# Control.net
KiCad netlist of a schematic drawn in Altium Designer
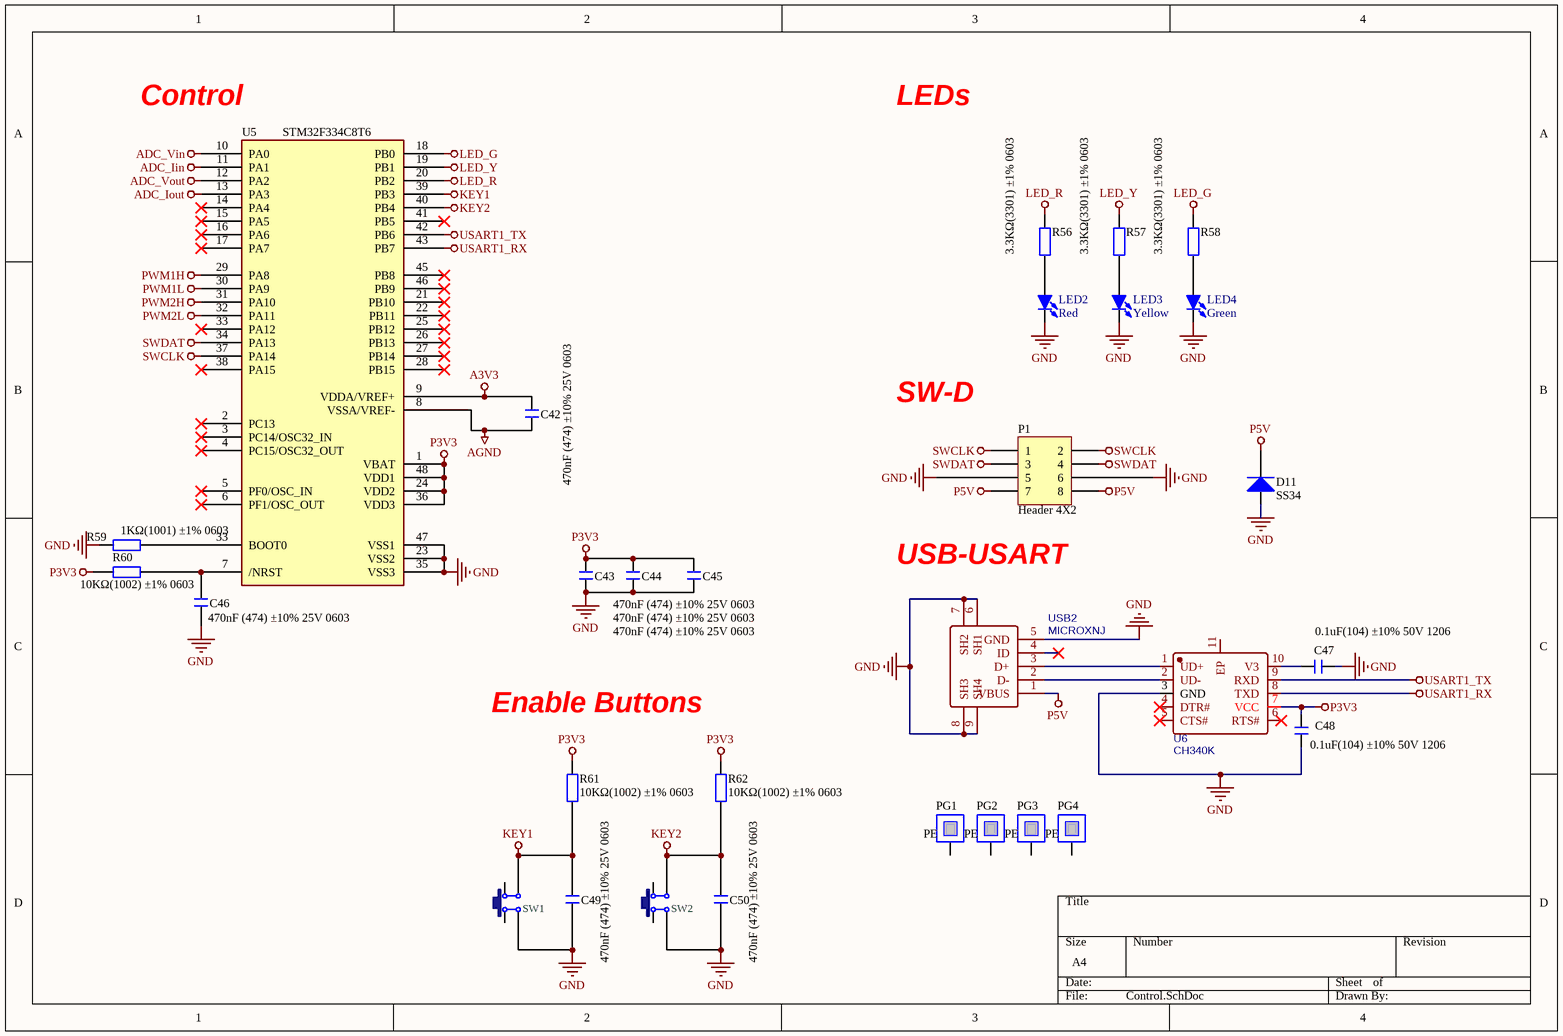
[diagram p0: Control.SchDoc]

(export (version "E")
  (design (tool "Eeschema 10.0.6"))
  (components
    (comp (ref "C42")
      (value "470nF (474) ±10% 25V 0603")
      (footprint "C 0603_L")
      (description "贴片电容")
      (libsource (lib "0.1 - 电阻-电容-电感") (part "C"))
    )
    (comp (ref "C43")
      (value "470nF (474) ±10% 25V 0603")
      (footprint "C 0603_L")
      (description "贴片电容")
      (libsource (lib "0.1 - 电阻-电容-电感") (part "C"))
    )
    (comp (ref "C44")
      (value "470nF (474) ±10% 25V 0603")
      (footprint "C 0603_L")
      (description "贴片电容")
      (libsource (lib "0.1 - 电阻-电容-电感") (part "C"))
    )
    (comp (ref "C45")
      (value "470nF (474) ±10% 25V 0603")
      (footprint "C 0603_L")
      (description "贴片电容")
      (libsource (lib "0.1 - 电阻-电容-电感") (part "C"))
    )
    (comp (ref "C46")
      (value "470nF (474) ±10% 25V 0603")
      (footprint "C 0603_L")
      (description "贴片电容")
      (libsource (lib "0.1 - 电阻-电容-电感") (part "C"))
    )
    (comp (ref "C47")
      (value "0.1uF(104) ±10% 50V 1206")
      (footprint "C 1206_M")
      (description "贴片电容")
      (libsource (lib "0.1 - 电阻-电容-电感") (part "C"))
    )
    (comp (ref "C48")
      (value "0.1uF(104) ±10% 50V 1206")
      (footprint "C 1206_M")
      (description "贴片电容")
      (libsource (lib "0.1 - 电阻-电容-电感") (part "C"))
    )
    (comp (ref "C49")
      (value "470nF (474) ±10% 25V 0603")
      (footprint "C 0603_L")
      (description "贴片电容")
      (libsource (lib "0.1 - 电阻-电容-电感") (part "C"))
    )
    (comp (ref "C50")
      (value "470nF (474) ±10% 25V 0603")
      (footprint "C 0603_L")
      (description "贴片电容")
      (libsource (lib "0.1 - 电阻-电容-电感") (part "C"))
    )
    (comp (ref "D11")
      (value "SS34")
      (footprint "SMA")
      (description "Default Diode")
      (libsource (lib "Miscellaneous Devices") (part "Diode"))
    )
    (comp (ref "LED2")
      (value "Red")
      (footprint "LED 0603R")
      (description "贴片LED")
      (fields (field (name "版权归属") "封装库来自淘宝 ID：黄晶宝石"))
      (libsource (lib "0.3 - LED发光二极管") (part "LED-SMD"))
    )
    (comp (ref "LED3")
      (value "Yellow")
      (footprint "LED 0603R")
      (description "贴片LED")
      (fields (field (name "版权归属") "封装库来自淘宝 ID：黄晶宝石"))
      (libsource (lib "0.3 - LED发光二极管") (part "LED-SMD"))
    )
    (comp (ref "LED4")
      (value "Green")
      (footprint "LED 0603R")
      (description "贴片LED")
      (fields (field (name "版权归属") "封装库来自淘宝 ID：黄晶宝石"))
      (libsource (lib "0.3 - LED发光二极管") (part "LED-SMD"))
    )
    (comp (ref "P1")
      (value "Header 4X2")
      (footprint "HDR2.54-LI-2x4P")
      (description "Header, 4-Pin, Dual row")
      (fields (field (name "PUBLISHER") "Altium Limited"))
      (libsource (lib "Miscellaneous Connectors") (part "Header 4X2"))
    )
    (comp (ref "PG1") (value "PE") (footprint "FG-M3") (libsource (lib "SYMBOL") (part "H-SINK")))
    (comp (ref "PG2") (value "PE") (footprint "FG-M3") (libsource (lib "SYMBOL") (part "H-SINK")))
    (comp (ref "PG3") (value "PE") (footprint "FG-M3") (libsource (lib "SYMBOL") (part "H-SINK")))
    (comp (ref "PG4") (value "PE") (footprint "FG-M3") (libsource (lib "SYMBOL") (part "H-SINK")))
    (comp (ref "R56")
      (value "3.3KΩ(3301) ±1% 0603")
      (footprint "R 0603_L")
      (description "贴片电阻")
      (fields (field (name "版权归属") "来自淘宝 ID：黄晶宝石"))
      (libsource (lib "0.1 - 电阻-电容-电感") (part "R"))
    )
    (comp (ref "R57")
      (value "3.3KΩ(3301) ±1% 0603")
      (footprint "R 0603_L")
      (description "贴片电阻")
      (fields (field (name "版权归属") "来自淘宝 ID：黄晶宝石"))
      (libsource (lib "0.1 - 电阻-电容-电感") (part "R"))
    )
    (comp (ref "R58")
      (value "3.3KΩ(3301) ±1% 0603")
      (footprint "R 0603_L")
      (description "贴片电阻")
      (fields (field (name "版权归属") "来自淘宝 ID：黄晶宝石"))
      (libsource (lib "0.1 - 电阻-电容-电感") (part "R"))
    )
    (comp (ref "R59")
      (value "1KΩ(1001) ±1% 0603")
      (footprint "R 0603_L")
      (description "贴片电阻")
      (fields (field (name "版权归属") "来自淘宝 ID：黄晶宝石"))
      (libsource (lib "0.1 - 电阻-电容-电感") (part "R"))
    )
    (comp (ref "R60")
      (value "10KΩ(1002) ±1% 0603")
      (footprint "R 0603_L")
      (description "贴片电阻")
      (fields (field (name "版权归属") "来自淘宝 ID：黄晶宝石"))
      (libsource (lib "0.1 - 电阻-电容-电感") (part "R"))
    )
    (comp (ref "R61")
      (value "10KΩ(1002) ±1% 0603")
      (footprint "R 0603_L")
      (description "贴片电阻")
      (fields (field (name "版权归属") "来自淘宝 ID：黄晶宝石"))
      (libsource (lib "0.1 - 电阻-电容-电感") (part "R"))
    )
    (comp (ref "R62")
      (value "10KΩ(1002) ±1% 0603")
      (footprint "R 0603_L")
      (description "贴片电阻")
      (fields (field (name "版权归属") "来自淘宝 ID：黄晶宝石"))
      (libsource (lib "0.1 - 电阻-电容-电感") (part "R"))
    )
    (comp (ref "SW1")
      (value "6x6x5")
      (footprint "TSW SMD-6*6*7")
      (description "直插6x6轻触开关")
      (fields (field (name "版权归属") "封装库来自淘宝 ID：黄晶宝石"))
      (libsource (lib "0.7 - 常用按键-开关") (part "TSW DIP-6x6"))
    )
    (comp (ref "SW2")
      (value "6x6x5")
      (footprint "TSW SMD-6*6*7")
      (description "直插6x6轻触开关")
      (fields (field (name "版权归属") "封装库来自淘宝 ID：黄晶宝石"))
      (libsource (lib "0.7 - 常用按键-开关") (part "TSW DIP-6x6"))
    )
    (comp (ref "U5")
      (value "STM32F334C8T6")
      (footprint "LQFP48-7*7")
      (libsource (lib "CBB012DV-V1.0") (part "STM32F334C8T6"))
    )
    (comp (ref "U6")
      (value "CH340K")
      (footprint "ESOP-10_L4.9-W3.9-P1.00-LS6.2-BL-EP")
      (fields (field (name "BOM_SUPPLIER PART") "C968586") (field (name "CONTRIBUTOR") "LCSC"))
      (libsource (lib "Portable power supply") (part "CH340K"))
    )
    (comp (ref "USB2")
      (value "MICROXNJ")
      (footprint "MICRO-USB-SMD_MICROXNJ")
      (fields
        (field (name "BOM_SUPPLIER PART") "C404969")
        (field (name "BOM_MANUFACTURER PART") "MicroXNJ")
        (field (name "CONTRIBUTOR") "LCSC")
      )
      (libsource (lib "Portable power supply") (part "MICROXNJ"))
    )
  )
  (nets
    (net (code "1") (name "A3V3") (class "Default")
      (node (ref "C42") (pin "2") (pinfunction "2_2") (pintype "passive"))
      (node (ref "U5") (pin "9") (pinfunction "VDDA/VREF+_9") (pintype "passive"))
    )
    (net (code "2") (name "ADC_Iin") (class "Default")
      (node (ref "U5") (pin "11") (pinfunction "PA1_11") (pintype "passive"))
    )
    (net (code "3") (name "ADC_Iout") (class "Default")
      (node (ref "U5") (pin "13") (pinfunction "PA3_13") (pintype "passive"))
    )
    (net (code "4") (name "ADC_Vin") (class "Default")
      (node (ref "U5") (pin "10") (pinfunction "PA0_10") (pintype "passive"))
    )
    (net (code "5") (name "ADC_Vout") (class "Default")
      (node (ref "U5") (pin "12") (pinfunction "PA2_12") (pintype "passive"))
    )
    (net (code "6") (name "AGND") (class "Default")
      (node (ref "C42") (pin "1") (pinfunction "1_1") (pintype "passive"))
      (node (ref "U5") (pin "8") (pinfunction "VSSA/VREF-_8") (pintype "passive"))
    )
    (net (code "7") (name "GND") (class "Default")
      (node (ref "C43") (pin "1") (pinfunction "1_1") (pintype "passive"))
      (node (ref "C44") (pin "1") (pinfunction "1_1") (pintype "passive"))
      (node (ref "C45") (pin "1") (pinfunction "1_1") (pintype "passive"))
      (node (ref "C46") (pin "1") (pinfunction "1_1") (pintype "passive"))
      (node (ref "C47") (pin "1") (pinfunction "1_1") (pintype "passive"))
      (node (ref "C48") (pin "2") (pinfunction "2_2") (pintype "passive"))
      (node (ref "C49") (pin "1") (pinfunction "1_1") (pintype "passive"))
      (node (ref "C50") (pin "1") (pinfunction "1_1") (pintype "passive"))
      (node (ref "D11") (pin "1") (pinfunction "A_1") (pintype "passive"))
      (node (ref "LED2") (pin "2") (pinfunction "K_2") (pintype "passive"))
      (node (ref "LED3") (pin "2") (pinfunction "K_2") (pintype "passive"))
      (node (ref "LED4") (pin "2") (pinfunction "K_2") (pintype "passive"))
      (node (ref "P1") (pin "5") (pinfunction "5_5") (pintype "passive"))
      (node (ref "P1") (pin "6") (pinfunction "6_6") (pintype "passive"))
      (node (ref "R59") (pin "1") (pinfunction "1_1") (pintype "passive"))
      (node (ref "SW1") (pin "4") (pinfunction "4_4") (pintype "passive"))
      (node (ref "SW2") (pin "4") (pinfunction "4_4") (pintype "passive"))
      (node (ref "U5") (pin "23") (pinfunction "VSS2_23") (pintype "passive"))
      (node (ref "U5") (pin "35") (pinfunction "VSS3_35") (pintype "passive"))
      (node (ref "U5") (pin "47") (pinfunction "VSS1_47") (pintype "passive"))
      (node (ref "U6") (pin "3") (pinfunction "GND_3") (pintype "passive"))
      (node (ref "USB2") (pin "5") (pinfunction "GND_5") (pintype "passive"))
      (node (ref "USB2") (pin "6") (pinfunction "SH1_6") (pintype "passive"))
      (node (ref "USB2") (pin "7") (pinfunction "SH2_7") (pintype "passive"))
      (node (ref "USB2") (pin "8") (pinfunction "SH3_8") (pintype "passive"))
      (node (ref "USB2") (pin "9") (pinfunction "SH4_9") (pintype "passive"))
    )
    (net (code "8") (name "KEY1") (class "Default")
      (node (ref "C49") (pin "2") (pinfunction "2_2") (pintype "passive"))
      (node (ref "R61") (pin "1") (pinfunction "1_1") (pintype "passive"))
      (node (ref "SW1") (pin "3") (pinfunction "3_3") (pintype "passive"))
      (node (ref "U5") (pin "39") (pinfunction "PB3_39") (pintype "passive"))
    )
    (net (code "9") (name "KEY2") (class "Default")
      (node (ref "C50") (pin "2") (pinfunction "2_2") (pintype "passive"))
      (node (ref "R62") (pin "1") (pinfunction "1_1") (pintype "passive"))
      (node (ref "SW2") (pin "3") (pinfunction "3_3") (pintype "passive"))
      (node (ref "U5") (pin "40") (pinfunction "PB4_40") (pintype "passive"))
    )
    (net (code "10") (name "LED_G") (class "Default")
      (node (ref "R58") (pin "2") (pinfunction "2_2") (pintype "passive"))
      (node (ref "U5") (pin "18") (pinfunction "PB0_18") (pintype "passive"))
    )
    (net (code "11") (name "LED_R") (class "Default")
      (node (ref "R56") (pin "2") (pinfunction "2_2") (pintype "passive"))
      (node (ref "U5") (pin "20") (pinfunction "PB2_20") (pintype "passive"))
    )
    (net (code "12") (name "LED_Y") (class "Default")
      (node (ref "R57") (pin "2") (pinfunction "2_2") (pintype "passive"))
      (node (ref "U5") (pin "19") (pinfunction "PB1_19") (pintype "passive"))
    )
    (net (code "13") (name "Net-(LED2-A)") (class "Default")
      (node (ref "LED2") (pin "1") (pinfunction "A_1") (pintype "passive"))
      (node (ref "R56") (pin "1") (pinfunction "1_1") (pintype "passive"))
    )
    (net (code "14") (name "Net-(LED3-A)") (class "Default")
      (node (ref "LED3") (pin "1") (pinfunction "A_1") (pintype "passive"))
      (node (ref "R57") (pin "1") (pinfunction "1_1") (pintype "passive"))
    )
    (net (code "15") (name "Net-(LED4-A)") (class "Default")
      (node (ref "LED4") (pin "1") (pinfunction "A_1") (pintype "passive"))
      (node (ref "R58") (pin "1") (pinfunction "1_1") (pintype "passive"))
    )
    (net (code "16") (name "Net-(U5-BOOT0)") (class "Default")
      (node (ref "R59") (pin "2") (pinfunction "2_2") (pintype "passive"))
      (node (ref "U5") (pin "33") (pinfunction "BOOT0_33") (pintype "passive"))
    )
    (net (code "17") (name "Net-(U5-{slash}NRST)") (class "Default")
      (node (ref "C46") (pin "2") (pinfunction "2_2") (pintype "passive"))
      (node (ref "R60") (pin "2") (pinfunction "2_2") (pintype "passive"))
      (node (ref "U5") (pin "7") (pinfunction "/NRST_7") (pintype "passive"))
    )
    (net (code "18") (name "Net-(U6-UD+)") (class "Default")
      (node (ref "U6") (pin "1") (pinfunction "UD+_1") (pintype "passive"))
      (node (ref "USB2") (pin "3") (pinfunction "D+_3") (pintype "passive"))
    )
    (net (code "19") (name "Net-(U6-UD-)") (class "Default")
      (node (ref "U6") (pin "2") (pinfunction "UD-_2") (pintype "passive"))
      (node (ref "USB2") (pin "2") (pinfunction "D-_2") (pintype "passive"))
    )
    (net (code "20") (name "Net-(U6-V3)") (class "Default")
      (node (ref "C47") (pin "2") (pinfunction "2_2") (pintype "passive"))
      (node (ref "U6") (pin "10") (pinfunction "V3_10") (pintype "passive"))
    )
    (net (code "21") (name "P3V3") (class "Default")
      (node (ref "C43") (pin "2") (pinfunction "2_2") (pintype "passive"))
      (node (ref "C44") (pin "2") (pinfunction "2_2") (pintype "passive"))
      (node (ref "C45") (pin "2") (pinfunction "2_2") (pintype "passive"))
      (node (ref "C48") (pin "1") (pinfunction "1_1") (pintype "passive"))
      (node (ref "R60") (pin "1") (pinfunction "1_1") (pintype "passive"))
      (node (ref "R61") (pin "2") (pinfunction "2_2") (pintype "passive"))
      (node (ref "R62") (pin "2") (pinfunction "2_2") (pintype "passive"))
      (node (ref "U5") (pin "1") (pinfunction "VBAT_1") (pintype "passive"))
      (node (ref "U5") (pin "24") (pinfunction "VDD2_24") (pintype "passive"))
      (node (ref "U5") (pin "36") (pinfunction "VDD3_36") (pintype "passive"))
      (node (ref "U5") (pin "48") (pinfunction "VDD1_48") (pintype "passive"))
      (node (ref "U6") (pin "7") (pinfunction "VCC_7") (pintype "passive"))
    )
    (net (code "22") (name "P5V") (class "Default")
      (node (ref "D11") (pin "2") (pinfunction "K_2") (pintype "passive"))
      (node (ref "P1") (pin "7") (pinfunction "7_7") (pintype "passive"))
      (node (ref "P1") (pin "8") (pinfunction "8_8") (pintype "passive"))
      (node (ref "USB2") (pin "1") (pinfunction "VBUS_1") (pintype "passive"))
    )
    (net (code "23") (name "PWM1H") (class "Default")
      (node (ref "U5") (pin "29") (pinfunction "PA8_29") (pintype "passive"))
    )
    (net (code "24") (name "PWM1L") (class "Default")
      (node (ref "U5") (pin "30") (pinfunction "PA9_30") (pintype "passive"))
    )
    (net (code "25") (name "PWM2H") (class "Default")
      (node (ref "U5") (pin "31") (pinfunction "PA10_31") (pintype "passive"))
    )
    (net (code "26") (name "PWM2L") (class "Default")
      (node (ref "U5") (pin "32") (pinfunction "PA11_32") (pintype "passive"))
    )
    (net (code "27") (name "SWCLK") (class "Default")
      (node (ref "P1") (pin "1") (pinfunction "1_1") (pintype "passive"))
      (node (ref "P1") (pin "2") (pinfunction "2_2") (pintype "passive"))
      (node (ref "U5") (pin "37") (pinfunction "PA14_37") (pintype "passive"))
    )
    (net (code "28") (name "SWDAT") (class "Default")
      (node (ref "P1") (pin "3") (pinfunction "3_3") (pintype "passive"))
      (node (ref "P1") (pin "4") (pinfunction "4_4") (pintype "passive"))
      (node (ref "U5") (pin "34") (pinfunction "PA13_34") (pintype "passive"))
    )
    (net (code "29") (name "USART1_RX") (class "Default")
      (node (ref "U5") (pin "43") (pinfunction "PB7_43") (pintype "passive"))
      (node (ref "U6") (pin "8") (pinfunction "TXD_8") (pintype "passive"))
    )
    (net (code "30") (name "USART1_TX") (class "Default")
      (node (ref "U5") (pin "42") (pinfunction "PB6_42") (pintype "passive"))
      (node (ref "U6") (pin "9") (pinfunction "RXD_9") (pintype "passive"))
    )
    (net (code "31") (name "unconnected-(PG1-Pad1)") (class "Default")
      (node (ref "PG1") (pin "1") (pinfunction "1_1") (pintype "passive"))
    )
    (net (code "32") (name "unconnected-(PG2-Pad1)") (class "Default")
      (node (ref "PG2") (pin "1") (pinfunction "1_1") (pintype "passive"))
    )
    (net (code "33") (name "unconnected-(PG3-Pad1)") (class "Default")
      (node (ref "PG3") (pin "1") (pinfunction "1_1") (pintype "passive"))
    )
    (net (code "34") (name "unconnected-(PG4-Pad1)") (class "Default")
      (node (ref "PG4") (pin "1") (pinfunction "1_1") (pintype "passive"))
    )
    (net (code "35") (name "unconnected-(SW1-Pad1)") (class "Default")
      (node (ref "SW1") (pin "1") (pinfunction "1_1") (pintype "passive"))
    )
    (net (code "36") (name "unconnected-(SW1-Pad2)") (class "Default")
      (node (ref "SW1") (pin "2") (pinfunction "2_2") (pintype "passive"))
    )
    (net (code "37") (name "unconnected-(SW2-Pad1)") (class "Default")
      (node (ref "SW2") (pin "1") (pinfunction "1_1") (pintype "passive"))
    )
    (net (code "38") (name "unconnected-(SW2-Pad2)") (class "Default")
      (node (ref "SW2") (pin "2") (pinfunction "2_2") (pintype "passive"))
    )
    (net (code "39") (name "unconnected-(U5-PA4-Pad14)") (class "Default")
      (node (ref "U5") (pin "14") (pinfunction "PA4_14") (pintype "passive+no_connect"))
    )
    (net (code "40") (name "unconnected-(U5-PA5-Pad15)") (class "Default")
      (node (ref "U5") (pin "15") (pinfunction "PA5_15") (pintype "passive+no_connect"))
    )
    (net (code "41") (name "unconnected-(U5-PA6-Pad16)") (class "Default")
      (node (ref "U5") (pin "16") (pinfunction "PA6_16") (pintype "passive+no_connect"))
    )
    (net (code "42") (name "unconnected-(U5-PA7-Pad17)") (class "Default")
      (node (ref "U5") (pin "17") (pinfunction "PA7_17") (pintype "passive+no_connect"))
    )
    (net (code "43") (name "unconnected-(U5-PA12-Pad33)") (class "Default")
      (node (ref "U5") (pin "33") (pinfunction "PA12_33") (pintype "passive+no_connect"))
    )
    (net (code "44") (name "unconnected-(U5-PA15-Pad38)") (class "Default")
      (node (ref "U5") (pin "38") (pinfunction "PA15_38") (pintype "passive+no_connect"))
    )
    (net (code "45") (name "unconnected-(U5-PB5-Pad41)") (class "Default")
      (node (ref "U5") (pin "41") (pinfunction "PB5_41") (pintype "passive+no_connect"))
    )
    (net (code "46") (name "unconnected-(U5-PB8-Pad45)") (class "Default")
      (node (ref "U5") (pin "45") (pinfunction "PB8_45") (pintype "passive+no_connect"))
    )
    (net (code "47") (name "unconnected-(U5-PB9-Pad46)") (class "Default")
      (node (ref "U5") (pin "46") (pinfunction "PB9_46") (pintype "passive+no_connect"))
    )
    (net (code "48") (name "unconnected-(U5-PB10-Pad21)") (class "Default")
      (node (ref "U5") (pin "21") (pinfunction "PB10_21") (pintype "passive+no_connect"))
    )
    (net (code "49") (name "unconnected-(U5-PB11-Pad22)") (class "Default")
      (node (ref "U5") (pin "22") (pinfunction "PB11_22") (pintype "passive+no_connect"))
    )
    (net (code "50") (name "unconnected-(U5-PB12-Pad25)") (class "Default")
      (node (ref "U5") (pin "25") (pinfunction "PB12_25") (pintype "passive+no_connect"))
    )
    (net (code "51") (name "unconnected-(U5-PB13-Pad26)") (class "Default")
      (node (ref "U5") (pin "26") (pinfunction "PB13_26") (pintype "passive+no_connect"))
    )
    (net (code "52") (name "unconnected-(U5-PB14-Pad27)") (class "Default")
      (node (ref "U5") (pin "27") (pinfunction "PB14_27") (pintype "passive+no_connect"))
    )
    (net (code "53") (name "unconnected-(U5-PB15-Pad28)") (class "Default")
      (node (ref "U5") (pin "28") (pinfunction "PB15_28") (pintype "passive+no_connect"))
    )
    (net (code "54") (name "unconnected-(U5-PC13-Pad2)") (class "Default")
      (node (ref "U5") (pin "2") (pinfunction "PC13_2") (pintype "passive+no_connect"))
    )
    (net (code "55") (name "unconnected-(U5-PC14{slash}OSC32_IN-Pad3)") (class "Default")
      (node (ref "U5") (pin "3") (pinfunction "PC14/OSC32_IN_3") (pintype "passive+no_connect"))
    )
    (net (code "56") (name "unconnected-(U5-PC15{slash}OSC32_OUT-Pad4)") (class "Default")
      (node (ref "U5") (pin "4") (pinfunction "PC15/OSC32_OUT_4") (pintype "passive+no_connect"))
    )
    (net (code "57") (name "unconnected-(U5-PF0{slash}OSC_IN-Pad5)") (class "Default")
      (node (ref "U5") (pin "5") (pinfunction "PF0/OSC_IN_5") (pintype "passive+no_connect"))
    )
    (net (code "58") (name "unconnected-(U5-PF1{slash}OSC_OUT-Pad6)") (class "Default")
      (node (ref "U5") (pin "6") (pinfunction "PF1/OSC_OUT_6") (pintype "passive+no_connect"))
    )
    (net (code "59") (name "unconnected-(U6-CTS#-Pad5)") (class "Default")
      (node (ref "U6") (pin "5") (pinfunction "CTS#_5") (pintype "passive+no_connect"))
    )
    (net (code "60") (name "unconnected-(U6-DTR#-Pad4)") (class "Default")
      (node (ref "U6") (pin "4") (pinfunction "DTR#_4") (pintype "passive+no_connect"))
    )
    (net (code "61") (name "unconnected-(U6-EP-Pad11)") (class "Default")
      (node (ref "U6") (pin "11") (pinfunction "EP_11") (pintype "passive"))
    )
    (net (code "62") (name "unconnected-(U6-RTS#-Pad6)") (class "Default")
      (node (ref "U6") (pin "6") (pinfunction "RTS#_6") (pintype "passive+no_connect"))
    )
    (net (code "63") (name "unconnected-(USB2-ID-Pad4)") (class "Default")
      (node (ref "USB2") (pin "4") (pinfunction "ID_4") (pintype "passive+no_connect"))
    )
  )
)
